# main.net
KiCad netlist of a schematic drawn in EAGLE
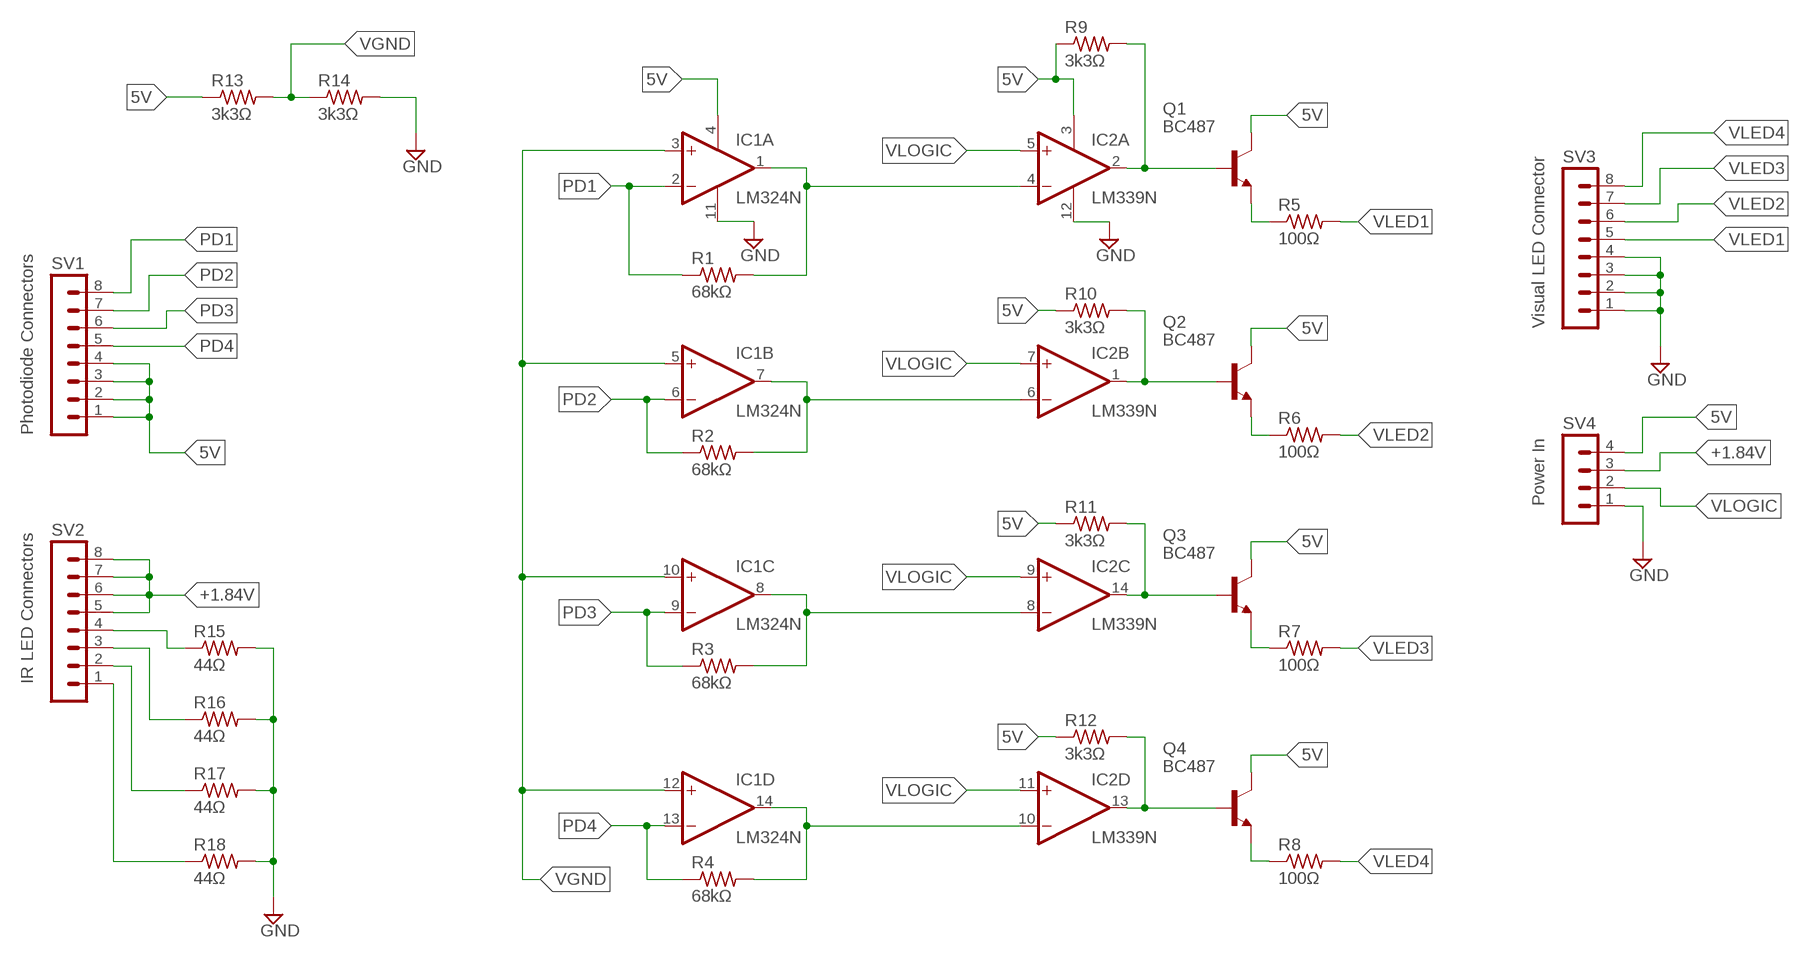
[diagram p0: schematic, sheet 1]

(export (version "E")
  (design (tool "Eeschema 10.0.6"))
  (components
    (comp (ref "IC1")
      (value "LM324N")
      (footprint "eagle-import:DIL14")
      (libsource (lib "eagle-import") (part "LM324N"))
    )
    (comp (ref "IC2")
      (value "LM339N")
      (footprint "eagle-import:DIL14")
      (libsource (lib "eagle-import") (part "LM339N"))
    )
    (comp (ref "Q1")
      (value "BC487")
      (footprint "eagle-import:TO92-EBC")
      (libsource (lib "eagle-import") (part "BC487"))
    )
    (comp (ref "Q2")
      (value "BC487")
      (footprint "eagle-import:TO92-EBC")
      (libsource (lib "eagle-import") (part "BC487"))
    )
    (comp (ref "Q3")
      (value "BC487")
      (footprint "eagle-import:TO92-EBC")
      (libsource (lib "eagle-import") (part "BC487"))
    )
    (comp (ref "Q4")
      (value "BC487")
      (footprint "eagle-import:TO92-EBC")
      (libsource (lib "eagle-import") (part "BC487"))
    )
    (comp (ref "R1")
      (value "68kΩ")
      (footprint "eagle-import:0204_7")
      (libsource (lib "eagle-import") (part "R-US_0204/7"))
    )
    (comp (ref "R2")
      (value "68kΩ")
      (footprint "eagle-import:0204_7")
      (libsource (lib "eagle-import") (part "R-US_0204/7"))
    )
    (comp (ref "R3")
      (value "68kΩ")
      (footprint "eagle-import:0204_7")
      (libsource (lib "eagle-import") (part "R-US_0204/7"))
    )
    (comp (ref "R4")
      (value "68kΩ")
      (footprint "eagle-import:0204_7")
      (libsource (lib "eagle-import") (part "R-US_0204/7"))
    )
    (comp (ref "R5")
      (value "100Ω")
      (footprint "eagle-import:0204_7")
      (libsource (lib "eagle-import") (part "R-US_0204/7"))
    )
    (comp (ref "R6")
      (value "100Ω")
      (footprint "eagle-import:0204_7")
      (libsource (lib "eagle-import") (part "R-US_0204/7"))
    )
    (comp (ref "R7")
      (value "100Ω")
      (footprint "eagle-import:0204_7")
      (libsource (lib "eagle-import") (part "R-US_0204/7"))
    )
    (comp (ref "R8")
      (value "100Ω")
      (footprint "eagle-import:0204_7")
      (libsource (lib "eagle-import") (part "R-US_0204/7"))
    )
    (comp (ref "R9")
      (value "3k3Ω")
      (footprint "eagle-import:0204_7")
      (libsource (lib "eagle-import") (part "R-US_0204/7"))
    )
    (comp (ref "R10")
      (value "3k3Ω")
      (footprint "eagle-import:0204_7")
      (libsource (lib "eagle-import") (part "R-US_0204/7"))
    )
    (comp (ref "R11")
      (value "3k3Ω")
      (footprint "eagle-import:0204_7")
      (libsource (lib "eagle-import") (part "R-US_0204/7"))
    )
    (comp (ref "R12")
      (value "3k3Ω")
      (footprint "eagle-import:0204_7")
      (libsource (lib "eagle-import") (part "R-US_0204/7"))
    )
    (comp (ref "R13")
      (value "3k3Ω")
      (footprint "eagle-import:0204_7")
      (libsource (lib "eagle-import") (part "R-US_0204/7"))
    )
    (comp (ref "R14")
      (value "3k3Ω")
      (footprint "eagle-import:0204_7")
      (libsource (lib "eagle-import") (part "R-US_0204/7"))
    )
    (comp (ref "R15")
      (value "44Ω")
      (footprint "eagle-import:0204_7")
      (libsource (lib "eagle-import") (part "R-US_0204/7"))
    )
    (comp (ref "R16")
      (value "44Ω")
      (footprint "eagle-import:0204_7")
      (libsource (lib "eagle-import") (part "R-US_0204/7"))
    )
    (comp (ref "R17")
      (value "44Ω")
      (footprint "eagle-import:0204_7")
      (libsource (lib "eagle-import") (part "R-US_0204/7"))
    )
    (comp (ref "R18")
      (value "44Ω")
      (footprint "eagle-import:0204_7")
      (libsource (lib "eagle-import") (part "R-US_0204/7"))
    )
    (comp (ref "SV1")
      (value "Photodiode Connectors")
      (footprint "eagle-import:MA08-1")
      (libsource (lib "eagle-import") (part "MA08-1"))
    )
    (comp (ref "SV2")
      (value "IR LED Connectors")
      (footprint "eagle-import:MA08-1")
      (libsource (lib "eagle-import") (part "MA08-1"))
    )
    (comp (ref "SV3")
      (value "Visual LED Connector")
      (footprint "eagle-import:MA08-1")
      (libsource (lib "eagle-import") (part "MA08-1"))
    )
    (comp (ref "SV4")
      (value "Power In")
      (footprint "eagle-import:MA04-1")
      (libsource (lib "eagle-import") (part "MA04-1"))
    )
  )
  (nets
    (net (code "1") (name "+1.84V") (class "Default")
      (node (ref "SV2") (pin "5") (pinfunction "5_5") (pintype "passive"))
      (node (ref "SV2") (pin "6") (pinfunction "6_6") (pintype "passive"))
      (node (ref "SV2") (pin "7") (pinfunction "7_7") (pintype "passive"))
      (node (ref "SV2") (pin "8") (pinfunction "8_8") (pintype "passive"))
      (node (ref "SV4") (pin "3") (pinfunction "3_3") (pintype "passive"))
    )
    (net (code "2") (name "5V") (class "Default")
      (node (ref "IC1") (pin "4") (pinfunction "V+_4") (pintype "power_in"))
      (node (ref "IC2") (pin "3") (pinfunction "V+_3") (pintype "power_in"))
      (node (ref "Q1") (pin "C") (pinfunction "C_C") (pintype "passive"))
      (node (ref "Q2") (pin "C") (pinfunction "C_C") (pintype "passive"))
      (node (ref "Q3") (pin "C") (pinfunction "C_C") (pintype "passive"))
      (node (ref "Q4") (pin "C") (pinfunction "C_C") (pintype "passive"))
      (node (ref "R10") (pin "1") (pinfunction "1_1") (pintype "passive"))
      (node (ref "R11") (pin "1") (pinfunction "1_1") (pintype "passive"))
      (node (ref "R12") (pin "1") (pinfunction "1_1") (pintype "passive"))
      (node (ref "R13") (pin "1") (pinfunction "1_1") (pintype "passive"))
      (node (ref "R9") (pin "1") (pinfunction "1_1") (pintype "passive"))
      (node (ref "SV1") (pin "1") (pinfunction "1_1") (pintype "passive"))
      (node (ref "SV1") (pin "2") (pinfunction "2_2") (pintype "passive"))
      (node (ref "SV1") (pin "3") (pinfunction "3_3") (pintype "passive"))
      (node (ref "SV1") (pin "4") (pinfunction "4_4") (pintype "passive"))
      (node (ref "SV4") (pin "4") (pinfunction "4_4") (pintype "passive"))
    )
    (net (code "3") (name "GND") (class "Default")
      (node (ref "IC1") (pin "11") (pinfunction "V-_11") (pintype "power_in"))
      (node (ref "IC2") (pin "12") (pinfunction "GND_12") (pintype "power_in"))
      (node (ref "R14") (pin "2") (pinfunction "2_2") (pintype "passive"))
      (node (ref "R15") (pin "2") (pinfunction "2_2") (pintype "passive"))
      (node (ref "R16") (pin "2") (pinfunction "2_2") (pintype "passive"))
      (node (ref "R17") (pin "2") (pinfunction "2_2") (pintype "passive"))
      (node (ref "R18") (pin "2") (pinfunction "2_2") (pintype "passive"))
      (node (ref "SV3") (pin "1") (pinfunction "1_1") (pintype "passive"))
      (node (ref "SV3") (pin "2") (pinfunction "2_2") (pintype "passive"))
      (node (ref "SV3") (pin "3") (pinfunction "3_3") (pintype "passive"))
      (node (ref "SV3") (pin "4") (pinfunction "4_4") (pintype "passive"))
      (node (ref "SV4") (pin "1") (pinfunction "1_1") (pintype "passive"))
    )
    (net (code "4") (name "Net-(IC1A-OUT)") (class "Default")
      (node (ref "IC1") (pin "1") (pinfunction "OUT_1") (pintype "output"))
      (node (ref "IC2") (pin "4") (pinfunction "-IN_4") (pintype "input"))
      (node (ref "R1") (pin "2") (pinfunction "2_2") (pintype "passive"))
    )
    (net (code "5") (name "Net-(IC1B-OUT)") (class "Default")
      (node (ref "IC1") (pin "7") (pinfunction "OUT_7") (pintype "output"))
      (node (ref "IC2") (pin "6") (pinfunction "-IN_6") (pintype "input"))
      (node (ref "R2") (pin "2") (pinfunction "2_2") (pintype "passive"))
    )
    (net (code "6") (name "Net-(IC1D-OUT)") (class "Default")
      (node (ref "IC1") (pin "14") (pinfunction "OUT_14") (pintype "output"))
      (node (ref "IC2") (pin "10") (pinfunction "-IN_10") (pintype "input"))
      (node (ref "R4") (pin "2") (pinfunction "2_2") (pintype "passive"))
    )
    (net (code "7") (name "Net-(IC2A-OUT)") (class "Default")
      (node (ref "IC2") (pin "2") (pinfunction "OUT_2") (pintype "open_collector"))
      (node (ref "Q1") (pin "B") (pinfunction "B_B") (pintype "passive"))
      (node (ref "R9") (pin "2") (pinfunction "2_2") (pintype "passive"))
    )
    (net (code "8") (name "Net-(IC2B-OUT)") (class "Default")
      (node (ref "IC2") (pin "1") (pinfunction "OUT_1") (pintype "open_collector"))
      (node (ref "Q2") (pin "B") (pinfunction "B_B") (pintype "passive"))
      (node (ref "R10") (pin "2") (pinfunction "2_2") (pintype "passive"))
    )
    (net (code "9") (name "Net-(IC2C-OUT)") (class "Default")
      (node (ref "IC2") (pin "14") (pinfunction "OUT_14") (pintype "open_collector"))
      (node (ref "Q3") (pin "B") (pinfunction "B_B") (pintype "passive"))
      (node (ref "R11") (pin "2") (pinfunction "2_2") (pintype "passive"))
    )
    (net (code "10") (name "Net-(IC2D-OUT)") (class "Default")
      (node (ref "IC2") (pin "13") (pinfunction "OUT_13") (pintype "open_collector"))
      (node (ref "Q4") (pin "B") (pinfunction "B_B") (pintype "passive"))
      (node (ref "R12") (pin "2") (pinfunction "2_2") (pintype "passive"))
    )
    (net (code "11") (name "Net-(Q1-PadE)") (class "Default")
      (node (ref "Q1") (pin "E") (pinfunction "E_E") (pintype "passive"))
      (node (ref "R5") (pin "1") (pinfunction "1_1") (pintype "passive"))
    )
    (net (code "12") (name "Net-(Q2-PadE)") (class "Default")
      (node (ref "Q2") (pin "E") (pinfunction "E_E") (pintype "passive"))
      (node (ref "R6") (pin "1") (pinfunction "1_1") (pintype "passive"))
    )
    (net (code "13") (name "Net-(Q3-PadE)") (class "Default")
      (node (ref "Q3") (pin "E") (pinfunction "E_E") (pintype "passive"))
      (node (ref "R7") (pin "1") (pinfunction "1_1") (pintype "passive"))
    )
    (net (code "14") (name "Net-(Q4-PadE)") (class "Default")
      (node (ref "Q4") (pin "E") (pinfunction "E_E") (pintype "passive"))
      (node (ref "R8") (pin "1") (pinfunction "1_1") (pintype "passive"))
    )
    (net (code "15") (name "Net-(R15-Pad1)") (class "Default")
      (node (ref "R15") (pin "1") (pinfunction "1_1") (pintype "passive"))
      (node (ref "SV2") (pin "4") (pinfunction "4_4") (pintype "passive"))
    )
    (net (code "16") (name "Net-(R16-Pad1)") (class "Default")
      (node (ref "R16") (pin "1") (pinfunction "1_1") (pintype "passive"))
      (node (ref "SV2") (pin "3") (pinfunction "3_3") (pintype "passive"))
    )
    (net (code "17") (name "Net-(R17-Pad1)") (class "Default")
      (node (ref "R17") (pin "1") (pinfunction "1_1") (pintype "passive"))
      (node (ref "SV2") (pin "2") (pinfunction "2_2") (pintype "passive"))
    )
    (net (code "18") (name "Net-(R18-Pad1)") (class "Default")
      (node (ref "R18") (pin "1") (pinfunction "1_1") (pintype "passive"))
      (node (ref "SV2") (pin "1") (pinfunction "1_1") (pintype "passive"))
    )
    (net (code "19") (name "PD1") (class "Default")
      (node (ref "IC1") (pin "2") (pinfunction "-IN_2") (pintype "input"))
      (node (ref "R1") (pin "1") (pinfunction "1_1") (pintype "passive"))
      (node (ref "SV1") (pin "8") (pinfunction "8_8") (pintype "passive"))
    )
    (net (code "20") (name "PD2") (class "Default")
      (node (ref "IC1") (pin "6") (pinfunction "-IN_6") (pintype "input"))
      (node (ref "R2") (pin "1") (pinfunction "1_1") (pintype "passive"))
      (node (ref "SV1") (pin "7") (pinfunction "7_7") (pintype "passive"))
    )
    (net (code "21") (name "PD3") (class "Default")
      (node (ref "IC1") (pin "9") (pinfunction "-IN_9") (pintype "input"))
      (node (ref "R3") (pin "1") (pinfunction "1_1") (pintype "passive"))
      (node (ref "SV1") (pin "6") (pinfunction "6_6") (pintype "passive"))
    )
    (net (code "22") (name "PD4") (class "Default")
      (node (ref "IC1") (pin "13") (pinfunction "-IN_13") (pintype "input"))
      (node (ref "R4") (pin "1") (pinfunction "1_1") (pintype "passive"))
      (node (ref "SV1") (pin "5") (pinfunction "5_5") (pintype "passive"))
    )
    (net (code "23") (name "VGND") (class "Default")
      (node (ref "IC1") (pin "10") (pinfunction "+IN_10") (pintype "input"))
      (node (ref "IC1") (pin "12") (pinfunction "+IN_12") (pintype "input"))
      (node (ref "IC1") (pin "3") (pinfunction "+IN_3") (pintype "input"))
      (node (ref "IC1") (pin "5") (pinfunction "+IN_5") (pintype "input"))
      (node (ref "R13") (pin "2") (pinfunction "2_2") (pintype "passive"))
      (node (ref "R14") (pin "1") (pinfunction "1_1") (pintype "passive"))
    )
    (net (code "24") (name "VLED1") (class "Default")
      (node (ref "R5") (pin "2") (pinfunction "2_2") (pintype "passive"))
      (node (ref "SV3") (pin "5") (pinfunction "5_5") (pintype "passive"))
    )
    (net (code "25") (name "VLED2") (class "Default")
      (node (ref "R6") (pin "2") (pinfunction "2_2") (pintype "passive"))
      (node (ref "SV3") (pin "6") (pinfunction "6_6") (pintype "passive"))
    )
    (net (code "26") (name "VLED3") (class "Default")
      (node (ref "R7") (pin "2") (pinfunction "2_2") (pintype "passive"))
      (node (ref "SV3") (pin "7") (pinfunction "7_7") (pintype "passive"))
    )
    (net (code "27") (name "VLED4") (class "Default")
      (node (ref "R8") (pin "2") (pinfunction "2_2") (pintype "passive"))
      (node (ref "SV3") (pin "8") (pinfunction "8_8") (pintype "passive"))
    )
    (net (code "28") (name "VLOGIC") (class "Default")
      (node (ref "IC1") (pin "8") (pinfunction "OUT_8") (pintype "output"))
      (node (ref "IC2") (pin "11") (pinfunction "+IN_11") (pintype "input"))
      (node (ref "IC2") (pin "5") (pinfunction "+IN_5") (pintype "input"))
      (node (ref "IC2") (pin "7") (pinfunction "+IN_7") (pintype "input"))
      (node (ref "IC2") (pin "8") (pinfunction "-IN_8") (pintype "input"))
      (node (ref "IC2") (pin "9") (pinfunction "+IN_9") (pintype "input"))
      (node (ref "R3") (pin "2") (pinfunction "2_2") (pintype "passive"))
      (node (ref "SV4") (pin "2") (pinfunction "2_2") (pintype "passive"))
    )
  )
)
